# CAN_transciever.net
KiCad netlist of a schematic drawn in Altium Designer
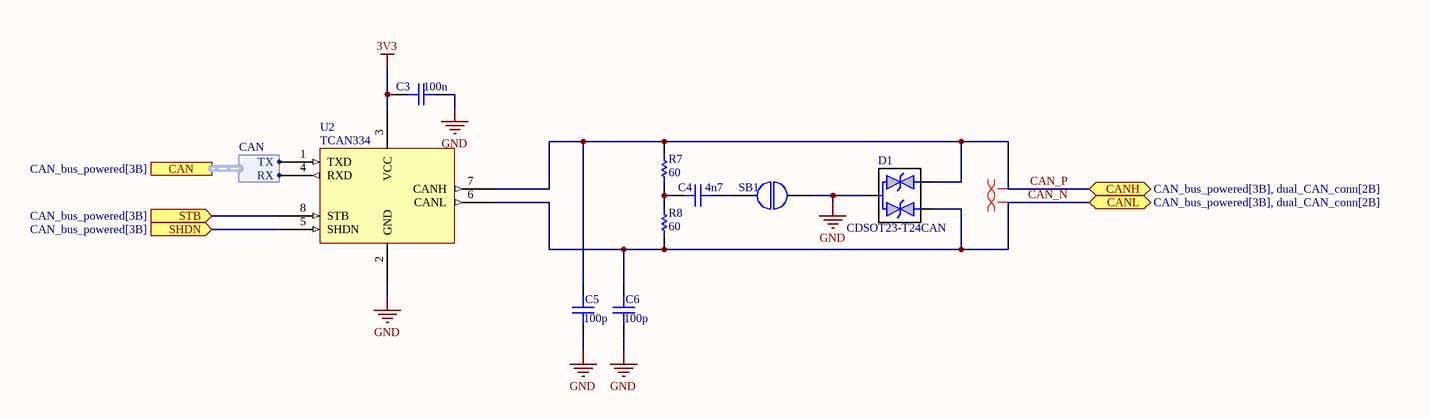
[diagram p0: CAN_transciever.SchDoc]

(export (version "E")
  (design (tool "Eeschema 10.0.6"))
  (components
    (comp (ref "C3")
      (value "100n")
      (footprint "CAP-0603-NP")
      (description "Capacitor")
      (libsource (lib "drfc_schlib") (part "Capacitor"))
    )
    (comp (ref "C4")
      (value "4n7")
      (footprint "CAP-0603-NP")
      (description "Capacitor")
      (libsource (lib "drfc_schlib") (part "Capacitor"))
    )
    (comp (ref "C5")
      (value "100p")
      (footprint "CAP-0603-NP")
      (description "Capacitor")
      (libsource (lib "drfc_schlib") (part "Capacitor"))
    )
    (comp (ref "C6")
      (value "100p")
      (footprint "CAP-0603-NP")
      (description "Capacitor")
      (libsource (lib "drfc_schlib") (part "Capacitor"))
    )
    (comp (ref "D1")
      (value "CDSOT23-T24CAN")
      (footprint "SOT23127P600-8N")
      (libsource (lib "drfc_schlib") (part "Dual TVS Diode"))
    )
    (comp (ref "R7")
      (value "60")
      (footprint "RES-0603")
      (description "Resistor")
      (libsource (lib "drfc_schlib") (part "Resistor"))
    )
    (comp (ref "R8")
      (value "60")
      (footprint "RES-0603")
      (description "Resistor")
      (libsource (lib "drfc_schlib") (part "Resistor"))
    )
    (comp (ref "SB1")
      (value "NO Solder Bridge")
      (footprint "Solder Bridge")
      (description "Normally Open Solder Bridge")
      (libsource (lib "drfc_schlib") (part "NO Solder Bridge"))
    )
    (comp (ref "U2")
      (value "TCAN334")
      (footprint "ST SOT23-5L")
      (description "Can tranciever with shutdown and standby with wake")
      (libsource (lib "drfc_schlib") (part "TCAN334"))
    )
  )
  (nets
    (net (code "2") (name "/CAN_N") (class "Default")
      (node (ref "C6") (pin "1") (pinfunction "1_1") (pintype "passive"))
      (node (ref "D1") (pin "1") (pinfunction "1_1") (pintype "passive"))
      (node (ref "R8") (pin "2") (pinfunction "2_2") (pintype "passive"))
      (node (ref "U2") (pin "6") (pinfunction "CANL_6") (pintype "output"))
    )
    (net (code "3") (name "/CAN_P") (class "Default")
      (node (ref "C5") (pin "1") (pinfunction "1_1") (pintype "passive"))
      (node (ref "D1") (pin "2") (pinfunction "2_2") (pintype "passive"))
      (node (ref "R7") (pin "1") (pinfunction "1_1") (pintype "passive"))
      (node (ref "U2") (pin "7") (pinfunction "CANH_7") (pintype "output"))
    )
    (net (code "4") (name "/RX") (class "Default")
      (node (ref "U2") (pin "4") (pinfunction "RXD_4") (pintype "output"))
    )
    (net (code "5") (name "/SHDN") (class "Default")
      (node (ref "U2") (pin "5") (pinfunction "SHDN_5") (pintype "input"))
    )
    (net (code "6") (name "/STB") (class "Default")
      (node (ref "U2") (pin "8") (pinfunction "STB_8") (pintype "input"))
    )
    (net (code "7") (name "/TX") (class "Default")
      (node (ref "U2") (pin "1") (pinfunction "TXD_1") (pintype "input"))
    )
    (net (code "9") (name "3V3") (class "Default")
      (node (ref "C3") (pin "2") (pinfunction "2_2") (pintype "passive"))
      (node (ref "U2") (pin "3") (pinfunction "VCC_3") (pintype "power_in"))
    )
    (net (code "10") (name "GND") (class "Default")
      (node (ref "C3") (pin "1") (pinfunction "1_1") (pintype "passive"))
      (node (ref "C5") (pin "2") (pinfunction "2_2") (pintype "passive"))
      (node (ref "C6") (pin "2") (pinfunction "2_2") (pintype "passive"))
      (node (ref "D1") (pin "3") (pinfunction "3_3") (pintype "passive"))
      (node (ref "SB1") (pin "1") (pinfunction "1_1") (pintype "open_collector"))
      (node (ref "U2") (pin "2") (pinfunction "GND_2") (pintype "power_in"))
    )
    (net (code "11") (name "Net-(C4-Pad1)") (class "Default")
      (node (ref "C4") (pin "1") (pinfunction "1_1") (pintype "passive"))
      (node (ref "SB1") (pin "2") (pinfunction "2_2") (pintype "open_collector"))
    )
    (net (code "12") (name "Net-(C4-Pad2)") (class "Default")
      (node (ref "C4") (pin "2") (pinfunction "2_2") (pintype "passive"))
      (node (ref "R7") (pin "2") (pinfunction "2_2") (pintype "passive"))
      (node (ref "R8") (pin "1") (pinfunction "1_1") (pintype "passive"))
    )
  )
)
